# schematic.net
KiCad netlist of a schematic drawn in EAGLE
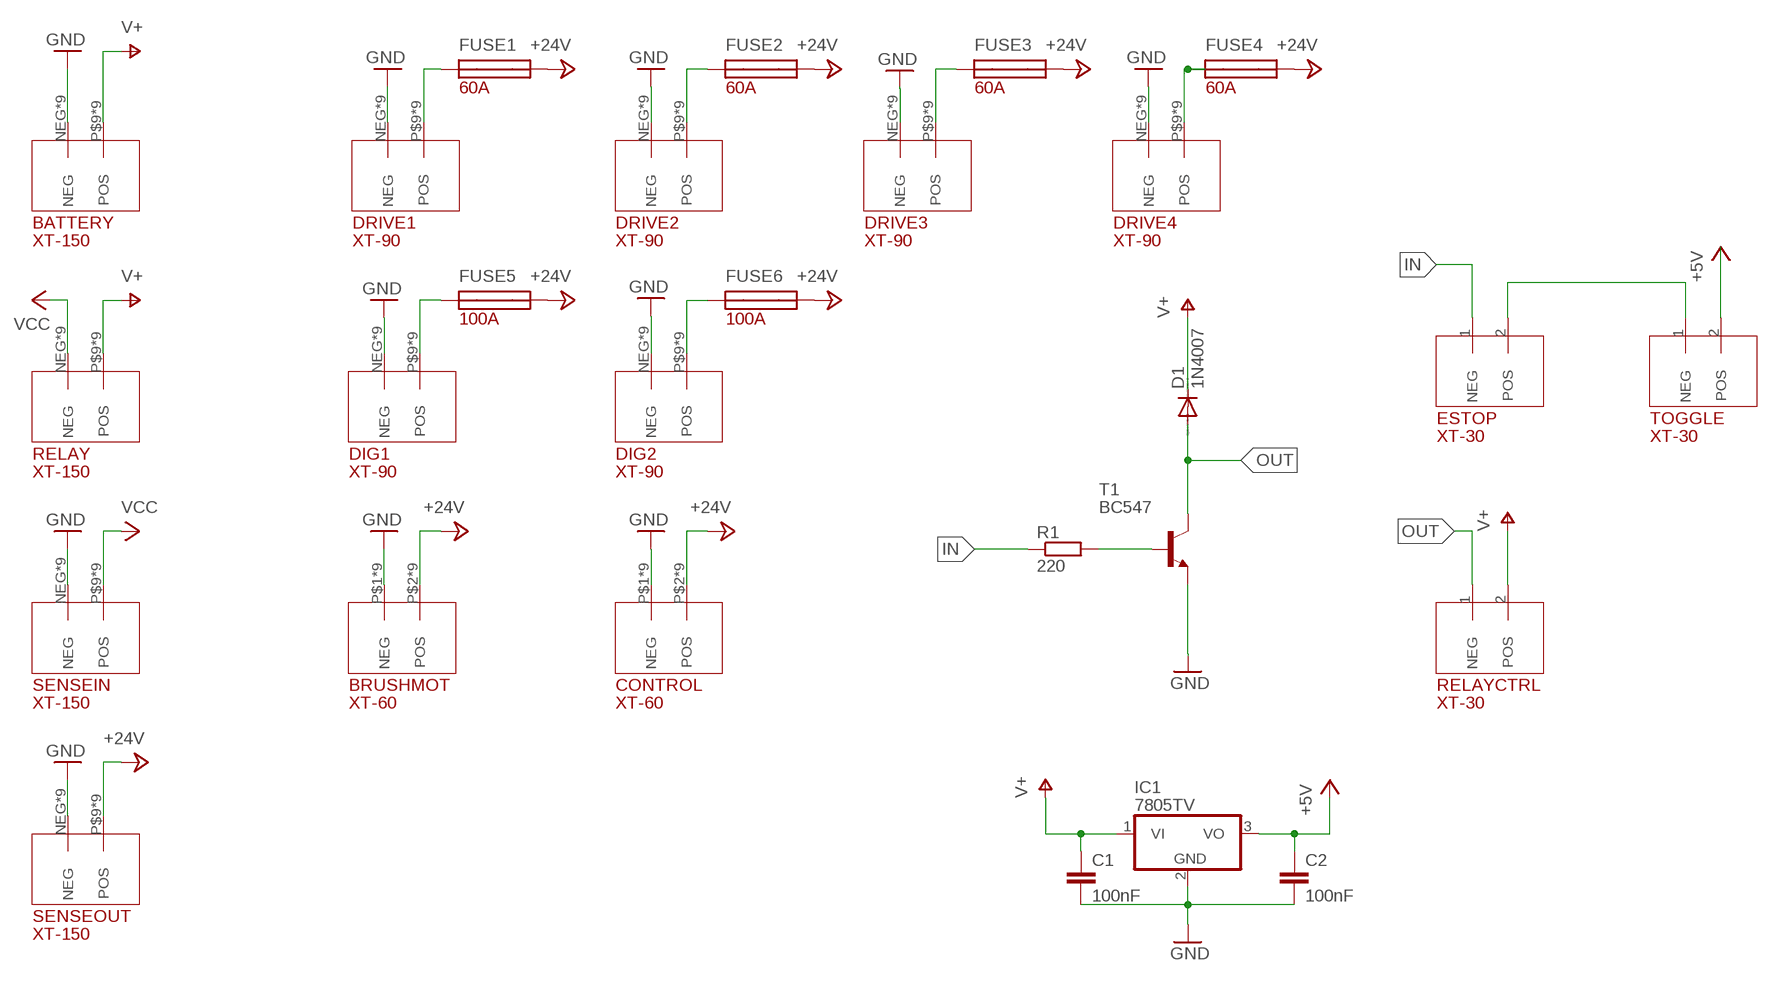
[diagram p0: schematic, sheet 1]

(export (version "E")
  (design (tool "Eeschema 10.0.6"))
  (components
    (comp (ref "BATTERY")
      (value "XT-150")
      (footprint "eagle-import:XT-150")
      (libsource (lib "eagle-import") (part "XT-150"))
    )
    (comp (ref "BRUSHMOT")
      (value "XT-60")
      (footprint "eagle-import:XT-60")
      (libsource (lib "eagle-import") (part "XT-60"))
    )
    (comp (ref "C1")
      (value "100nF")
      (footprint "eagle-import:C5B5")
      (libsource (lib "eagle-import") (part "C5/5"))
    )
    (comp (ref "C2")
      (value "100nF")
      (footprint "eagle-import:C5B5")
      (libsource (lib "eagle-import") (part "C5/5"))
    )
    (comp (ref "CONTROL")
      (value "XT-60")
      (footprint "eagle-import:XT-60")
      (libsource (lib "eagle-import") (part "XT-60"))
    )
    (comp (ref "D1")
      (value "1N4007")
      (footprint "eagle-import:DO41-10")
      (libsource (lib "eagle-import") (part "1N4004"))
    )
    (comp (ref "DIG1")
      (value "XT-90")
      (footprint "eagle-import:XT-90")
      (libsource (lib "eagle-import") (part "XT-90"))
    )
    (comp (ref "DIG2")
      (value "XT-90")
      (footprint "eagle-import:XT-90")
      (libsource (lib "eagle-import") (part "XT-90"))
    )
    (comp (ref "DRIVE1")
      (value "XT-90")
      (footprint "eagle-import:XT-90")
      (libsource (lib "eagle-import") (part "XT-90"))
    )
    (comp (ref "DRIVE2")
      (value "XT-90")
      (footprint "eagle-import:XT-90")
      (libsource (lib "eagle-import") (part "XT-90"))
    )
    (comp (ref "DRIVE3")
      (value "XT-90")
      (footprint "eagle-import:XT-90")
      (libsource (lib "eagle-import") (part "XT-90"))
    )
    (comp (ref "DRIVE4")
      (value "XT-90")
      (footprint "eagle-import:XT-90")
      (libsource (lib "eagle-import") (part "XT-90"))
    )
    (comp (ref "ESTOP")
      (value "XT-30")
      (footprint "eagle-import:XT-30")
      (libsource (lib "eagle-import") (part "XT-30"))
    )
    (comp (ref "FUSE1")
      (value "60A")
      (footprint "eagle-import:3555")
      (libsource (lib "eagle-import") (part "FUSE"))
    )
    (comp (ref "FUSE2")
      (value "60A")
      (footprint "eagle-import:3555")
      (libsource (lib "eagle-import") (part "FUSE"))
    )
    (comp (ref "FUSE3")
      (value "60A")
      (footprint "eagle-import:3555")
      (libsource (lib "eagle-import") (part "FUSE"))
    )
    (comp (ref "FUSE4")
      (value "60A")
      (footprint "eagle-import:3555")
      (libsource (lib "eagle-import") (part "FUSE"))
    )
    (comp (ref "FUSE5")
      (value "100A")
      (footprint "eagle-import:3555")
      (libsource (lib "eagle-import") (part "FUSE"))
    )
    (comp (ref "FUSE6")
      (value "100A")
      (footprint "eagle-import:3555")
      (libsource (lib "eagle-import") (part "FUSE"))
    )
    (comp (ref "IC1")
      (value "7805TV")
      (footprint "eagle-import:TO220V")
      (libsource (lib "eagle-import") (part "78TV05"))
    )
    (comp (ref "R1")
      (value "220")
      (footprint "eagle-import:0204_7")
      (libsource (lib "eagle-import") (part "R-EU_0204/7"))
    )
    (comp (ref "RELAY")
      (value "XT-150")
      (footprint "eagle-import:XT-150")
      (libsource (lib "eagle-import") (part "XT-150"))
    )
    (comp (ref "RELAYCTRL")
      (value "XT-30")
      (footprint "eagle-import:XT-30")
      (libsource (lib "eagle-import") (part "XT-30"))
    )
    (comp (ref "SENSEIN")
      (value "XT-150")
      (footprint "eagle-import:XT-150")
      (libsource (lib "eagle-import") (part "XT-150"))
    )
    (comp (ref "SENSEOUT")
      (value "XT-150")
      (footprint "eagle-import:XT-150")
      (libsource (lib "eagle-import") (part "XT-150"))
    )
    (comp (ref "T1")
      (value "BC547")
      (footprint "eagle-import:TO92")
      (libsource (lib "eagle-import") (part "BC547"))
    )
    (comp (ref "TOGGLE")
      (value "XT-30")
      (footprint "eagle-import:XT-30")
      (libsource (lib "eagle-import") (part "XT-30"))
    )
  )
  (nets
    (net (code "1") (name "+5V") (class "Default")
      (node (ref "C2") (pin "1") (pinfunction "1_1") (pintype "passive"))
      (node (ref "IC1") (pin "3") (pinfunction "VO_3") (pintype "passive"))
      (node (ref "TOGGLE") (pin "2") (pinfunction "POS_2") (pintype "bidirectional"))
    )
    (net (code "2") (name "+24V") (class "Default")
      (node (ref "BRUSHMOT") (pin "P$10") (pinfunction "POS_P$10") (pintype "bidirectional"))
      (node (ref "BRUSHMOT") (pin "P$11") (pinfunction "POS_P$11") (pintype "bidirectional"))
      (node (ref "BRUSHMOT") (pin "P$12") (pinfunction "POS_P$12") (pintype "bidirectional"))
      (node (ref "BRUSHMOT") (pin "P$13") (pinfunction "POS_P$13") (pintype "bidirectional"))
      (node (ref "BRUSHMOT") (pin "P$14") (pinfunction "POS_P$14") (pintype "bidirectional"))
      (node (ref "BRUSHMOT") (pin "P$2") (pinfunction "POS_P$2") (pintype "bidirectional"))
      (node (ref "BRUSHMOT") (pin "P$7") (pinfunction "POS_P$7") (pintype "bidirectional"))
      (node (ref "BRUSHMOT") (pin "P$8") (pinfunction "POS_P$8") (pintype "bidirectional"))
      (node (ref "BRUSHMOT") (pin "P$9") (pinfunction "POS_P$9") (pintype "bidirectional"))
      (node (ref "CONTROL") (pin "P$10") (pinfunction "POS_P$10") (pintype "bidirectional"))
      (node (ref "CONTROL") (pin "P$11") (pinfunction "POS_P$11") (pintype "bidirectional"))
      (node (ref "CONTROL") (pin "P$12") (pinfunction "POS_P$12") (pintype "bidirectional"))
      (node (ref "CONTROL") (pin "P$13") (pinfunction "POS_P$13") (pintype "bidirectional"))
      (node (ref "CONTROL") (pin "P$14") (pinfunction "POS_P$14") (pintype "bidirectional"))
      (node (ref "CONTROL") (pin "P$2") (pinfunction "POS_P$2") (pintype "bidirectional"))
      (node (ref "CONTROL") (pin "P$7") (pinfunction "POS_P$7") (pintype "bidirectional"))
      (node (ref "CONTROL") (pin "P$8") (pinfunction "POS_P$8") (pintype "bidirectional"))
      (node (ref "CONTROL") (pin "P$9") (pinfunction "POS_P$9") (pintype "bidirectional"))
      (node (ref "FUSE1") (pin "P$3") (pinfunction "P$2_P$3") (pintype "bidirectional"))
      (node (ref "FUSE1") (pin "P$4") (pinfunction "P$2_P$4") (pintype "bidirectional"))
      (node (ref "FUSE2") (pin "P$3") (pinfunction "P$2_P$3") (pintype "bidirectional"))
      (node (ref "FUSE2") (pin "P$4") (pinfunction "P$2_P$4") (pintype "bidirectional"))
      (node (ref "FUSE3") (pin "P$3") (pinfunction "P$2_P$3") (pintype "bidirectional"))
      (node (ref "FUSE3") (pin "P$4") (pinfunction "P$2_P$4") (pintype "bidirectional"))
      (node (ref "FUSE4") (pin "P$3") (pinfunction "P$2_P$3") (pintype "bidirectional"))
      (node (ref "FUSE4") (pin "P$4") (pinfunction "P$2_P$4") (pintype "bidirectional"))
      (node (ref "FUSE5") (pin "P$3") (pinfunction "P$2_P$3") (pintype "bidirectional"))
      (node (ref "FUSE5") (pin "P$4") (pinfunction "P$2_P$4") (pintype "bidirectional"))
      (node (ref "FUSE6") (pin "P$3") (pinfunction "P$2_P$3") (pintype "bidirectional"))
      (node (ref "FUSE6") (pin "P$4") (pinfunction "P$2_P$4") (pintype "bidirectional"))
      (node (ref "SENSEOUT") (pin "P$10") (pinfunction "POS_P$10") (pintype "bidirectional"))
      (node (ref "SENSEOUT") (pin "P$11") (pinfunction "POS_P$11") (pintype "bidirectional"))
      (node (ref "SENSEOUT") (pin "P$12") (pinfunction "POS_P$12") (pintype "bidirectional"))
      (node (ref "SENSEOUT") (pin "P$13") (pinfunction "POS_P$13") (pintype "bidirectional"))
      (node (ref "SENSEOUT") (pin "P$14") (pinfunction "POS_P$14") (pintype "bidirectional"))
      (node (ref "SENSEOUT") (pin "P$15") (pinfunction "POS_P$15") (pintype "bidirectional"))
      (node (ref "SENSEOUT") (pin "P$16") (pinfunction "POS_P$16") (pintype "bidirectional"))
      (node (ref "SENSEOUT") (pin "P$9") (pinfunction "POS_P$9") (pintype "bidirectional"))
      (node (ref "SENSEOUT") (pin "POS") (pinfunction "POS_POS") (pintype "bidirectional"))
    )
    (net (code "3") (name "GND") (class "Default")
      (node (ref "BATTERY") (pin "NEG") (pinfunction "NEG_NEG") (pintype "bidirectional"))
      (node (ref "BATTERY") (pin "P$1") (pinfunction "NEG_P$1") (pintype "bidirectional"))
      (node (ref "BATTERY") (pin "P$2") (pinfunction "NEG_P$2") (pintype "bidirectional"))
      (node (ref "BATTERY") (pin "P$3") (pinfunction "NEG_P$3") (pintype "bidirectional"))
      (node (ref "BATTERY") (pin "P$4") (pinfunction "NEG_P$4") (pintype "bidirectional"))
      (node (ref "BATTERY") (pin "P$5") (pinfunction "NEG_P$5") (pintype "bidirectional"))
      (node (ref "BATTERY") (pin "P$6") (pinfunction "NEG_P$6") (pintype "bidirectional"))
      (node (ref "BATTERY") (pin "P$7") (pinfunction "NEG_P$7") (pintype "bidirectional"))
      (node (ref "BATTERY") (pin "P$8") (pinfunction "NEG_P$8") (pintype "bidirectional"))
      (node (ref "BRUSHMOT") (pin "P$1") (pinfunction "NEG_P$1") (pintype "bidirectional"))
      (node (ref "BRUSHMOT") (pin "P$15") (pinfunction "NEG_P$15") (pintype "bidirectional"))
      (node (ref "BRUSHMOT") (pin "P$16") (pinfunction "NEG_P$16") (pintype "bidirectional"))
      (node (ref "BRUSHMOT") (pin "P$17") (pinfunction "NEG_P$17") (pintype "bidirectional"))
      (node (ref "BRUSHMOT") (pin "P$18") (pinfunction "NEG_P$18") (pintype "bidirectional"))
      (node (ref "BRUSHMOT") (pin "P$3") (pinfunction "NEG_P$3") (pintype "bidirectional"))
      (node (ref "BRUSHMOT") (pin "P$4") (pinfunction "NEG_P$4") (pintype "bidirectional"))
      (node (ref "BRUSHMOT") (pin "P$5") (pinfunction "NEG_P$5") (pintype "bidirectional"))
      (node (ref "BRUSHMOT") (pin "P$6") (pinfunction "NEG_P$6") (pintype "bidirectional"))
      (node (ref "C1") (pin "2") (pinfunction "2_2") (pintype "passive"))
      (node (ref "C2") (pin "2") (pinfunction "2_2") (pintype "passive"))
      (node (ref "CONTROL") (pin "P$1") (pinfunction "NEG_P$1") (pintype "bidirectional"))
      (node (ref "CONTROL") (pin "P$15") (pinfunction "NEG_P$15") (pintype "bidirectional"))
      (node (ref "CONTROL") (pin "P$16") (pinfunction "NEG_P$16") (pintype "bidirectional"))
      (node (ref "CONTROL") (pin "P$17") (pinfunction "NEG_P$17") (pintype "bidirectional"))
      (node (ref "CONTROL") (pin "P$18") (pinfunction "NEG_P$18") (pintype "bidirectional"))
      (node (ref "CONTROL") (pin "P$3") (pinfunction "NEG_P$3") (pintype "bidirectional"))
      (node (ref "CONTROL") (pin "P$4") (pinfunction "NEG_P$4") (pintype "bidirectional"))
      (node (ref "CONTROL") (pin "P$5") (pinfunction "NEG_P$5") (pintype "bidirectional"))
      (node (ref "CONTROL") (pin "P$6") (pinfunction "NEG_P$6") (pintype "bidirectional"))
      (node (ref "DIG1") (pin "NEG") (pinfunction "NEG_NEG") (pintype "bidirectional"))
      (node (ref "DIG1") (pin "P$1") (pinfunction "NEG_P$1") (pintype "bidirectional"))
      (node (ref "DIG1") (pin "P$2") (pinfunction "NEG_P$2") (pintype "bidirectional"))
      (node (ref "DIG1") (pin "P$3") (pinfunction "NEG_P$3") (pintype "bidirectional"))
      (node (ref "DIG1") (pin "P$4") (pinfunction "NEG_P$4") (pintype "bidirectional"))
      (node (ref "DIG1") (pin "P$5") (pinfunction "NEG_P$5") (pintype "bidirectional"))
      (node (ref "DIG1") (pin "P$6") (pinfunction "NEG_P$6") (pintype "bidirectional"))
      (node (ref "DIG1") (pin "P$7") (pinfunction "NEG_P$7") (pintype "bidirectional"))
      (node (ref "DIG1") (pin "P$8") (pinfunction "NEG_P$8") (pintype "bidirectional"))
      (node (ref "DIG2") (pin "NEG") (pinfunction "NEG_NEG") (pintype "bidirectional"))
      (node (ref "DIG2") (pin "P$1") (pinfunction "NEG_P$1") (pintype "bidirectional"))
      (node (ref "DIG2") (pin "P$2") (pinfunction "NEG_P$2") (pintype "bidirectional"))
      (node (ref "DIG2") (pin "P$3") (pinfunction "NEG_P$3") (pintype "bidirectional"))
      (node (ref "DIG2") (pin "P$4") (pinfunction "NEG_P$4") (pintype "bidirectional"))
      (node (ref "DIG2") (pin "P$5") (pinfunction "NEG_P$5") (pintype "bidirectional"))
      (node (ref "DIG2") (pin "P$6") (pinfunction "NEG_P$6") (pintype "bidirectional"))
      (node (ref "DIG2") (pin "P$7") (pinfunction "NEG_P$7") (pintype "bidirectional"))
      (node (ref "DIG2") (pin "P$8") (pinfunction "NEG_P$8") (pintype "bidirectional"))
      (node (ref "DRIVE1") (pin "NEG") (pinfunction "NEG_NEG") (pintype "bidirectional"))
      (node (ref "DRIVE1") (pin "P$1") (pinfunction "NEG_P$1") (pintype "bidirectional"))
      (node (ref "DRIVE1") (pin "P$2") (pinfunction "NEG_P$2") (pintype "bidirectional"))
      (node (ref "DRIVE1") (pin "P$3") (pinfunction "NEG_P$3") (pintype "bidirectional"))
      (node (ref "DRIVE1") (pin "P$4") (pinfunction "NEG_P$4") (pintype "bidirectional"))
      (node (ref "DRIVE1") (pin "P$5") (pinfunction "NEG_P$5") (pintype "bidirectional"))
      (node (ref "DRIVE1") (pin "P$6") (pinfunction "NEG_P$6") (pintype "bidirectional"))
      (node (ref "DRIVE1") (pin "P$7") (pinfunction "NEG_P$7") (pintype "bidirectional"))
      (node (ref "DRIVE1") (pin "P$8") (pinfunction "NEG_P$8") (pintype "bidirectional"))
      (node (ref "DRIVE2") (pin "NEG") (pinfunction "NEG_NEG") (pintype "bidirectional"))
      (node (ref "DRIVE2") (pin "P$1") (pinfunction "NEG_P$1") (pintype "bidirectional"))
      (node (ref "DRIVE2") (pin "P$2") (pinfunction "NEG_P$2") (pintype "bidirectional"))
      (node (ref "DRIVE2") (pin "P$3") (pinfunction "NEG_P$3") (pintype "bidirectional"))
      (node (ref "DRIVE2") (pin "P$4") (pinfunction "NEG_P$4") (pintype "bidirectional"))
      (node (ref "DRIVE2") (pin "P$5") (pinfunction "NEG_P$5") (pintype "bidirectional"))
      (node (ref "DRIVE2") (pin "P$6") (pinfunction "NEG_P$6") (pintype "bidirectional"))
      (node (ref "DRIVE2") (pin "P$7") (pinfunction "NEG_P$7") (pintype "bidirectional"))
      (node (ref "DRIVE2") (pin "P$8") (pinfunction "NEG_P$8") (pintype "bidirectional"))
      (node (ref "DRIVE3") (pin "NEG") (pinfunction "NEG_NEG") (pintype "bidirectional"))
      (node (ref "DRIVE3") (pin "P$1") (pinfunction "NEG_P$1") (pintype "bidirectional"))
      (node (ref "DRIVE3") (pin "P$2") (pinfunction "NEG_P$2") (pintype "bidirectional"))
      (node (ref "DRIVE3") (pin "P$3") (pinfunction "NEG_P$3") (pintype "bidirectional"))
      (node (ref "DRIVE3") (pin "P$4") (pinfunction "NEG_P$4") (pintype "bidirectional"))
      (node (ref "DRIVE3") (pin "P$5") (pinfunction "NEG_P$5") (pintype "bidirectional"))
      (node (ref "DRIVE3") (pin "P$6") (pinfunction "NEG_P$6") (pintype "bidirectional"))
      (node (ref "DRIVE3") (pin "P$7") (pinfunction "NEG_P$7") (pintype "bidirectional"))
      (node (ref "DRIVE3") (pin "P$8") (pinfunction "NEG_P$8") (pintype "bidirectional"))
      (node (ref "DRIVE4") (pin "NEG") (pinfunction "NEG_NEG") (pintype "bidirectional"))
      (node (ref "DRIVE4") (pin "P$1") (pinfunction "NEG_P$1") (pintype "bidirectional"))
      (node (ref "DRIVE4") (pin "P$2") (pinfunction "NEG_P$2") (pintype "bidirectional"))
      (node (ref "DRIVE4") (pin "P$3") (pinfunction "NEG_P$3") (pintype "bidirectional"))
      (node (ref "DRIVE4") (pin "P$4") (pinfunction "NEG_P$4") (pintype "bidirectional"))
      (node (ref "DRIVE4") (pin "P$5") (pinfunction "NEG_P$5") (pintype "bidirectional"))
      (node (ref "DRIVE4") (pin "P$6") (pinfunction "NEG_P$6") (pintype "bidirectional"))
      (node (ref "DRIVE4") (pin "P$7") (pinfunction "NEG_P$7") (pintype "bidirectional"))
      (node (ref "DRIVE4") (pin "P$8") (pinfunction "NEG_P$8") (pintype "bidirectional"))
      (node (ref "IC1") (pin "2") (pinfunction "GND_2") (pintype "passive"))
      (node (ref "SENSEIN") (pin "NEG") (pinfunction "NEG_NEG") (pintype "bidirectional"))
      (node (ref "SENSEIN") (pin "P$1") (pinfunction "NEG_P$1") (pintype "bidirectional"))
      (node (ref "SENSEIN") (pin "P$2") (pinfunction "NEG_P$2") (pintype "bidirectional"))
      (node (ref "SENSEIN") (pin "P$3") (pinfunction "NEG_P$3") (pintype "bidirectional"))
      (node (ref "SENSEIN") (pin "P$4") (pinfunction "NEG_P$4") (pintype "bidirectional"))
      (node (ref "SENSEIN") (pin "P$5") (pinfunction "NEG_P$5") (pintype "bidirectional"))
      (node (ref "SENSEIN") (pin "P$6") (pinfunction "NEG_P$6") (pintype "bidirectional"))
      (node (ref "SENSEIN") (pin "P$7") (pinfunction "NEG_P$7") (pintype "bidirectional"))
      (node (ref "SENSEIN") (pin "P$8") (pinfunction "NEG_P$8") (pintype "bidirectional"))
      (node (ref "SENSEOUT") (pin "NEG") (pinfunction "NEG_NEG") (pintype "bidirectional"))
      (node (ref "SENSEOUT") (pin "P$1") (pinfunction "NEG_P$1") (pintype "bidirectional"))
      (node (ref "SENSEOUT") (pin "P$2") (pinfunction "NEG_P$2") (pintype "bidirectional"))
      (node (ref "SENSEOUT") (pin "P$3") (pinfunction "NEG_P$3") (pintype "bidirectional"))
      (node (ref "SENSEOUT") (pin "P$4") (pinfunction "NEG_P$4") (pintype "bidirectional"))
      (node (ref "SENSEOUT") (pin "P$5") (pinfunction "NEG_P$5") (pintype "bidirectional"))
      (node (ref "SENSEOUT") (pin "P$6") (pinfunction "NEG_P$6") (pintype "bidirectional"))
      (node (ref "SENSEOUT") (pin "P$7") (pinfunction "NEG_P$7") (pintype "bidirectional"))
      (node (ref "SENSEOUT") (pin "P$8") (pinfunction "NEG_P$8") (pintype "bidirectional"))
      (node (ref "T1") (pin "1") (pinfunction "E_1") (pintype "passive"))
    )
    (net (code "4") (name "IN") (class "Default")
      (node (ref "ESTOP") (pin "1") (pinfunction "NEG_1") (pintype "bidirectional"))
      (node (ref "R1") (pin "1") (pinfunction "1_1") (pintype "passive"))
    )
    (net (code "5") (name "Net-(DIG1-POS-PadP$10)") (class "Default")
      (node (ref "DIG1") (pin "P$10") (pinfunction "POS_P$10") (pintype "bidirectional"))
      (node (ref "DIG1") (pin "P$11") (pinfunction "POS_P$11") (pintype "bidirectional"))
      (node (ref "DIG1") (pin "P$12") (pinfunction "POS_P$12") (pintype "bidirectional"))
      (node (ref "DIG1") (pin "P$13") (pinfunction "POS_P$13") (pintype "bidirectional"))
      (node (ref "DIG1") (pin "P$14") (pinfunction "POS_P$14") (pintype "bidirectional"))
      (node (ref "DIG1") (pin "P$15") (pinfunction "POS_P$15") (pintype "bidirectional"))
      (node (ref "DIG1") (pin "P$16") (pinfunction "POS_P$16") (pintype "bidirectional"))
      (node (ref "DIG1") (pin "P$9") (pinfunction "POS_P$9") (pintype "bidirectional"))
      (node (ref "DIG1") (pin "POS") (pinfunction "POS_POS") (pintype "bidirectional"))
      (node (ref "FUSE5") (pin "P$1") (pinfunction "P$1_P$1") (pintype "bidirectional"))
      (node (ref "FUSE5") (pin "P$2") (pinfunction "P$1_P$2") (pintype "bidirectional"))
    )
    (net (code "6") (name "Net-(DIG2-POS-PadP$10)") (class "Default")
      (node (ref "DIG2") (pin "P$10") (pinfunction "POS_P$10") (pintype "bidirectional"))
      (node (ref "DIG2") (pin "P$11") (pinfunction "POS_P$11") (pintype "bidirectional"))
      (node (ref "DIG2") (pin "P$12") (pinfunction "POS_P$12") (pintype "bidirectional"))
      (node (ref "DIG2") (pin "P$13") (pinfunction "POS_P$13") (pintype "bidirectional"))
      (node (ref "DIG2") (pin "P$14") (pinfunction "POS_P$14") (pintype "bidirectional"))
      (node (ref "DIG2") (pin "P$15") (pinfunction "POS_P$15") (pintype "bidirectional"))
      (node (ref "DIG2") (pin "P$16") (pinfunction "POS_P$16") (pintype "bidirectional"))
      (node (ref "DIG2") (pin "P$9") (pinfunction "POS_P$9") (pintype "bidirectional"))
      (node (ref "DIG2") (pin "POS") (pinfunction "POS_POS") (pintype "bidirectional"))
      (node (ref "FUSE6") (pin "P$1") (pinfunction "P$1_P$1") (pintype "bidirectional"))
      (node (ref "FUSE6") (pin "P$2") (pinfunction "P$1_P$2") (pintype "bidirectional"))
    )
    (net (code "7") (name "Net-(DRIVE1-POS-PadP$10)") (class "Default")
      (node (ref "DRIVE1") (pin "P$10") (pinfunction "POS_P$10") (pintype "bidirectional"))
      (node (ref "DRIVE1") (pin "P$11") (pinfunction "POS_P$11") (pintype "bidirectional"))
      (node (ref "DRIVE1") (pin "P$12") (pinfunction "POS_P$12") (pintype "bidirectional"))
      (node (ref "DRIVE1") (pin "P$13") (pinfunction "POS_P$13") (pintype "bidirectional"))
      (node (ref "DRIVE1") (pin "P$14") (pinfunction "POS_P$14") (pintype "bidirectional"))
      (node (ref "DRIVE1") (pin "P$15") (pinfunction "POS_P$15") (pintype "bidirectional"))
      (node (ref "DRIVE1") (pin "P$16") (pinfunction "POS_P$16") (pintype "bidirectional"))
      (node (ref "DRIVE1") (pin "P$9") (pinfunction "POS_P$9") (pintype "bidirectional"))
      (node (ref "DRIVE1") (pin "POS") (pinfunction "POS_POS") (pintype "bidirectional"))
      (node (ref "FUSE1") (pin "P$1") (pinfunction "P$1_P$1") (pintype "bidirectional"))
      (node (ref "FUSE1") (pin "P$2") (pinfunction "P$1_P$2") (pintype "bidirectional"))
    )
    (net (code "8") (name "Net-(DRIVE2-POS-PadP$10)") (class "Default")
      (node (ref "DRIVE2") (pin "P$10") (pinfunction "POS_P$10") (pintype "bidirectional"))
      (node (ref "DRIVE2") (pin "P$11") (pinfunction "POS_P$11") (pintype "bidirectional"))
      (node (ref "DRIVE2") (pin "P$12") (pinfunction "POS_P$12") (pintype "bidirectional"))
      (node (ref "DRIVE2") (pin "P$13") (pinfunction "POS_P$13") (pintype "bidirectional"))
      (node (ref "DRIVE2") (pin "P$14") (pinfunction "POS_P$14") (pintype "bidirectional"))
      (node (ref "DRIVE2") (pin "P$15") (pinfunction "POS_P$15") (pintype "bidirectional"))
      (node (ref "DRIVE2") (pin "P$16") (pinfunction "POS_P$16") (pintype "bidirectional"))
      (node (ref "DRIVE2") (pin "P$9") (pinfunction "POS_P$9") (pintype "bidirectional"))
      (node (ref "DRIVE2") (pin "POS") (pinfunction "POS_POS") (pintype "bidirectional"))
      (node (ref "FUSE2") (pin "P$1") (pinfunction "P$1_P$1") (pintype "bidirectional"))
      (node (ref "FUSE2") (pin "P$2") (pinfunction "P$1_P$2") (pintype "bidirectional"))
    )
    (net (code "9") (name "Net-(DRIVE3-POS-PadP$10)") (class "Default")
      (node (ref "DRIVE3") (pin "P$10") (pinfunction "POS_P$10") (pintype "bidirectional"))
      (node (ref "DRIVE3") (pin "P$11") (pinfunction "POS_P$11") (pintype "bidirectional"))
      (node (ref "DRIVE3") (pin "P$12") (pinfunction "POS_P$12") (pintype "bidirectional"))
      (node (ref "DRIVE3") (pin "P$13") (pinfunction "POS_P$13") (pintype "bidirectional"))
      (node (ref "DRIVE3") (pin "P$14") (pinfunction "POS_P$14") (pintype "bidirectional"))
      (node (ref "DRIVE3") (pin "P$15") (pinfunction "POS_P$15") (pintype "bidirectional"))
      (node (ref "DRIVE3") (pin "P$16") (pinfunction "POS_P$16") (pintype "bidirectional"))
      (node (ref "DRIVE3") (pin "P$9") (pinfunction "POS_P$9") (pintype "bidirectional"))
      (node (ref "DRIVE3") (pin "POS") (pinfunction "POS_POS") (pintype "bidirectional"))
      (node (ref "FUSE3") (pin "P$1") (pinfunction "P$1_P$1") (pintype "bidirectional"))
      (node (ref "FUSE3") (pin "P$2") (pinfunction "P$1_P$2") (pintype "bidirectional"))
    )
    (net (code "10") (name "Net-(DRIVE4-POS-PadP$10)") (class "Default")
      (node (ref "DRIVE4") (pin "P$10") (pinfunction "POS_P$10") (pintype "bidirectional"))
      (node (ref "DRIVE4") (pin "P$11") (pinfunction "POS_P$11") (pintype "bidirectional"))
      (node (ref "DRIVE4") (pin "P$12") (pinfunction "POS_P$12") (pintype "bidirectional"))
      (node (ref "DRIVE4") (pin "P$13") (pinfunction "POS_P$13") (pintype "bidirectional"))
      (node (ref "DRIVE4") (pin "P$14") (pinfunction "POS_P$14") (pintype "bidirectional"))
      (node (ref "DRIVE4") (pin "P$15") (pinfunction "POS_P$15") (pintype "bidirectional"))
      (node (ref "DRIVE4") (pin "P$16") (pinfunction "POS_P$16") (pintype "bidirectional"))
      (node (ref "DRIVE4") (pin "P$9") (pinfunction "POS_P$9") (pintype "bidirectional"))
      (node (ref "DRIVE4") (pin "POS") (pinfunction "POS_POS") (pintype "bidirectional"))
      (node (ref "FUSE4") (pin "P$1") (pinfunction "P$1_P$1") (pintype "bidirectional"))
      (node (ref "FUSE4") (pin "P$2") (pinfunction "P$1_P$2") (pintype "bidirectional"))
    )
    (net (code "11") (name "Net-(ESTOP-POS)") (class "Default")
      (node (ref "ESTOP") (pin "2") (pinfunction "POS_2") (pintype "bidirectional"))
      (node (ref "TOGGLE") (pin "1") (pinfunction "NEG_1") (pintype "bidirectional"))
    )
    (net (code "12") (name "Net-(T1-B)") (class "Default")
      (node (ref "R1") (pin "2") (pinfunction "2_2") (pintype "passive"))
      (node (ref "T1") (pin "2") (pinfunction "B_2") (pintype "passive"))
    )
    (net (code "13") (name "OUT") (class "Default")
      (node (ref "D1") (pin "A") (pinfunction "A_A") (pintype "passive"))
      (node (ref "RELAYCTRL") (pin "1") (pinfunction "NEG_1") (pintype "bidirectional"))
      (node (ref "T1") (pin "3") (pinfunction "C_3") (pintype "passive"))
    )
    (net (code "14") (name "V+") (class "Default")
      (node (ref "BATTERY") (pin "P$10") (pinfunction "POS_P$10") (pintype "bidirectional"))
      (node (ref "BATTERY") (pin "P$11") (pinfunction "POS_P$11") (pintype "bidirectional"))
      (node (ref "BATTERY") (pin "P$12") (pinfunction "POS_P$12") (pintype "bidirectional"))
      (node (ref "BATTERY") (pin "P$13") (pinfunction "POS_P$13") (pintype "bidirectional"))
      (node (ref "BATTERY") (pin "P$14") (pinfunction "POS_P$14") (pintype "bidirectional"))
      (node (ref "BATTERY") (pin "P$15") (pinfunction "POS_P$15") (pintype "bidirectional"))
      (node (ref "BATTERY") (pin "P$16") (pinfunction "POS_P$16") (pintype "bidirectional"))
      (node (ref "BATTERY") (pin "P$9") (pinfunction "POS_P$9") (pintype "bidirectional"))
      (node (ref "BATTERY") (pin "POS") (pinfunction "POS_POS") (pintype "bidirectional"))
      (node (ref "C1") (pin "1") (pinfunction "1_1") (pintype "passive"))
      (node (ref "D1") (pin "C") (pinfunction "C_C") (pintype "passive"))
      (node (ref "IC1") (pin "1") (pinfunction "VI_1") (pintype "input"))
      (node (ref "RELAY") (pin "P$10") (pinfunction "POS_P$10") (pintype "bidirectional"))
      (node (ref "RELAY") (pin "P$11") (pinfunction "POS_P$11") (pintype "bidirectional"))
      (node (ref "RELAY") (pin "P$12") (pinfunction "POS_P$12") (pintype "bidirectional"))
      (node (ref "RELAY") (pin "P$13") (pinfunction "POS_P$13") (pintype "bidirectional"))
      (node (ref "RELAY") (pin "P$14") (pinfunction "POS_P$14") (pintype "bidirectional"))
      (node (ref "RELAY") (pin "P$15") (pinfunction "POS_P$15") (pintype "bidirectional"))
      (node (ref "RELAY") (pin "P$16") (pinfunction "POS_P$16") (pintype "bidirectional"))
      (node (ref "RELAY") (pin "P$9") (pinfunction "POS_P$9") (pintype "bidirectional"))
      (node (ref "RELAY") (pin "POS") (pinfunction "POS_POS") (pintype "bidirectional"))
      (node (ref "RELAYCTRL") (pin "2") (pinfunction "POS_2") (pintype "bidirectional"))
    )
    (net (code "15") (name "VCC") (class "Default")
      (node (ref "RELAY") (pin "NEG") (pinfunction "NEG_NEG") (pintype "bidirectional"))
      (node (ref "RELAY") (pin "P$1") (pinfunction "NEG_P$1") (pintype "bidirectional"))
      (node (ref "RELAY") (pin "P$2") (pinfunction "NEG_P$2") (pintype "bidirectional"))
      (node (ref "RELAY") (pin "P$3") (pinfunction "NEG_P$3") (pintype "bidirectional"))
      (node (ref "RELAY") (pin "P$4") (pinfunction "NEG_P$4") (pintype "bidirectional"))
      (node (ref "RELAY") (pin "P$5") (pinfunction "NEG_P$5") (pintype "bidirectional"))
      (node (ref "RELAY") (pin "P$6") (pinfunction "NEG_P$6") (pintype "bidirectional"))
      (node (ref "RELAY") (pin "P$7") (pinfunction "NEG_P$7") (pintype "bidirectional"))
      (node (ref "RELAY") (pin "P$8") (pinfunction "NEG_P$8") (pintype "bidirectional"))
      (node (ref "SENSEIN") (pin "P$10") (pinfunction "POS_P$10") (pintype "bidirectional"))
      (node (ref "SENSEIN") (pin "P$11") (pinfunction "POS_P$11") (pintype "bidirectional"))
      (node (ref "SENSEIN") (pin "P$12") (pinfunction "POS_P$12") (pintype "bidirectional"))
      (node (ref "SENSEIN") (pin "P$13") (pinfunction "POS_P$13") (pintype "bidirectional"))
      (node (ref "SENSEIN") (pin "P$14") (pinfunction "POS_P$14") (pintype "bidirectional"))
      (node (ref "SENSEIN") (pin "P$15") (pinfunction "POS_P$15") (pintype "bidirectional"))
      (node (ref "SENSEIN") (pin "P$16") (pinfunction "POS_P$16") (pintype "bidirectional"))
      (node (ref "SENSEIN") (pin "P$9") (pinfunction "POS_P$9") (pintype "bidirectional"))
      (node (ref "SENSEIN") (pin "POS") (pinfunction "POS_POS") (pintype "bidirectional"))
    )
  )
)
